# LNA_DIV.net
KiCad netlist of a schematic drawn in Altium Designer
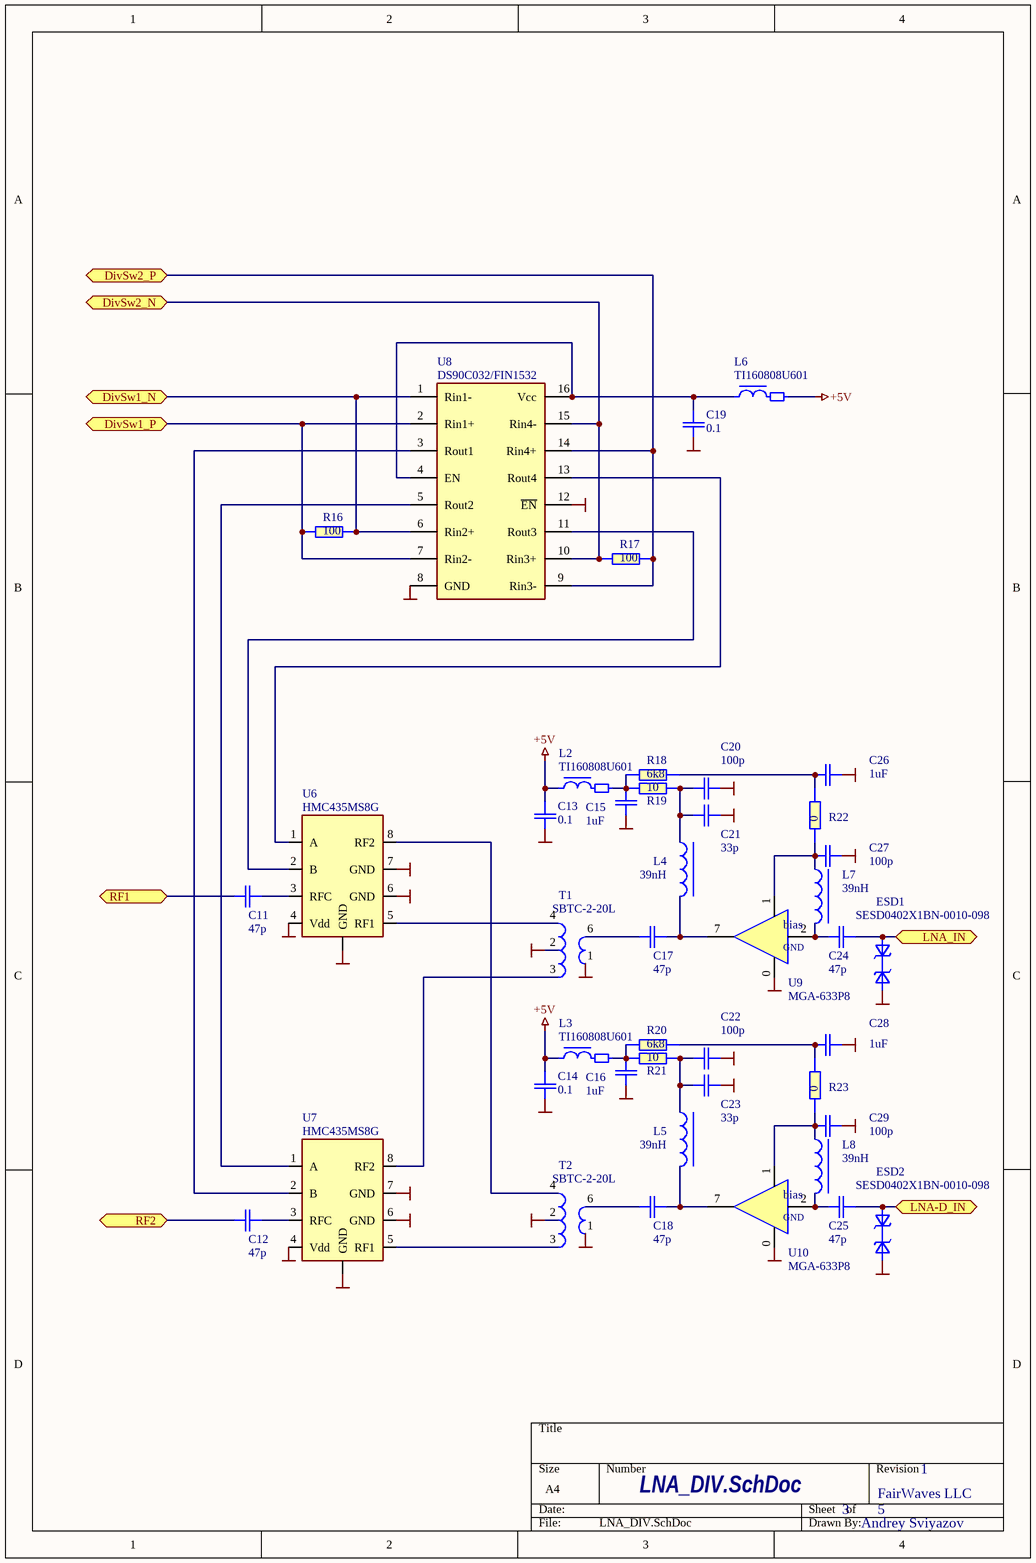
[diagram p0: LNA_DIV.SchDoc]

(export (version "E")
  (design (tool "Eeschema 10.0.6"))
  (components
    (comp (ref "C11")
      (value "47p")
      (footprint "C0603-PHILLIPS")
      (description "Capacitor")
      (fields (field (name "MANUFACTURER") "MURATA") (field (name "TOLERANCE") "20%"))
      (libsource (lib "altium-import") (part "root_1_C0603_"))
    )
    (comp (ref "C12")
      (value "47p")
      (footprint "C0603-PHILLIPS")
      (description "Capacitor")
      (fields (field (name "MANUFACTURER") "MURATA") (field (name "TOLERANCE") "20%"))
      (libsource (lib "altium-import") (part "root_1_C0603_"))
    )
    (comp (ref "C13")
      (value "0.1")
      (footprint "C0603-Phillips")
      (description "Capacitor")
      (fields (field (name "MANUFACTURER") "MURATA") (field (name "TOLERANCE") "20%"))
      (libsource (lib "Capacitors") (part "C0603"))
    )
    (comp (ref "C14")
      (value "0.1")
      (footprint "C0603-Phillips")
      (description "Capacitor")
      (fields (field (name "MANUFACTURER") "MURATA") (field (name "TOLERANCE") "20%"))
      (libsource (lib "Capacitors") (part "C0603"))
    )
    (comp (ref "C15")
      (value "1uF")
      (footprint "C0603-Phillips")
      (description "Capacitor")
      (fields (field (name "MANUFACTURER") "MURATA") (field (name "TOLERANCE") "20%"))
      (libsource (lib "Capacitors") (part "C0603"))
    )
    (comp (ref "C16")
      (value "1uF")
      (footprint "C0603-Phillips")
      (description "Capacitor")
      (fields (field (name "MANUFACTURER") "MURATA") (field (name "TOLERANCE") "20%"))
      (libsource (lib "Capacitors") (part "C0603"))
    )
    (comp (ref "C17")
      (value "47p")
      (footprint "C0603-PHILLIPS")
      (description "Capacitor")
      (fields (field (name "MANUFACTURER") "MURATA") (field (name "TOLERANCE") "20%"))
      (libsource (lib "altium-import") (part "root_1_C0603_"))
    )
    (comp (ref "C18")
      (value "47p")
      (footprint "C0603-PHILLIPS")
      (description "Capacitor")
      (fields (field (name "MANUFACTURER") "MURATA") (field (name "TOLERANCE") "20%"))
      (libsource (lib "altium-import") (part "root_1_C0603_"))
    )
    (comp (ref "C19")
      (value "0.1")
      (footprint "C0603-Phillips")
      (description "Capacitor")
      (fields (field (name "MANUFACTURER") "MURATA") (field (name "TOLERANCE") "20%"))
      (libsource (lib "Capacitors") (part "C0603"))
    )
    (comp (ref "C20")
      (value "100p")
      (footprint "C0603-PHILLIPS")
      (description "Capacitor")
      (fields (field (name "MANUFACTURER") "MURATA") (field (name "TOLERANCE") "20%"))
      (libsource (lib "altium-import") (part "root_1_C0603_"))
    )
    (comp (ref "C21")
      (value "33p")
      (footprint "C0603-PHILLIPS")
      (description "Capacitor")
      (fields (field (name "MANUFACTURER") "MURATA") (field (name "TOLERANCE") "20%"))
      (libsource (lib "altium-import") (part "root_1_C0603_"))
    )
    (comp (ref "C22")
      (value "100p")
      (footprint "C0603-PHILLIPS")
      (description "Capacitor")
      (fields (field (name "MANUFACTURER") "MURATA") (field (name "TOLERANCE") "20%"))
      (libsource (lib "altium-import") (part "root_1_C0603_"))
    )
    (comp (ref "C23")
      (value "33p")
      (footprint "C0603-PHILLIPS")
      (description "Capacitor")
      (fields (field (name "MANUFACTURER") "MURATA") (field (name "TOLERANCE") "20%"))
      (libsource (lib "altium-import") (part "root_1_C0603_"))
    )
    (comp (ref "C24")
      (value "47p")
      (footprint "C0603-PHILLIPS")
      (description "Capacitor")
      (fields (field (name "MANUFACTURER") "MURATA") (field (name "TOLERANCE") "20%"))
      (libsource (lib "altium-import") (part "root_1_C0603_"))
    )
    (comp (ref "C25")
      (value "47p")
      (footprint "C0603-PHILLIPS")
      (description "Capacitor")
      (fields (field (name "MANUFACTURER") "MURATA") (field (name "TOLERANCE") "20%"))
      (libsource (lib "altium-import") (part "root_1_C0603_"))
    )
    (comp (ref "C26")
      (value "1uF")
      (footprint "C0603-Phillips")
      (description "Capacitor")
      (fields (field (name "MANUFACTURER") "MURATA") (field (name "TOLERANCE") "20%"))
      (libsource (lib "Capacitors") (part "C0603"))
    )
    (comp (ref "C27")
      (value "100p")
      (footprint "C0603-PHILLIPS")
      (description "Capacitor")
      (fields (field (name "MANUFACTURER") "MURATA") (field (name "TOLERANCE") "20%"))
      (libsource (lib "altium-import") (part "root_1_C0603_"))
    )
    (comp (ref "C28")
      (value "1uF")
      (footprint "C0603-Phillips")
      (description "Capacitor")
      (fields (field (name "MANUFACTURER") "MURATA") (field (name "TOLERANCE") "20%"))
      (libsource (lib "Capacitors") (part "C0603"))
    )
    (comp (ref "C29")
      (value "100p")
      (footprint "C0603-PHILLIPS")
      (description "Capacitor")
      (fields (field (name "MANUFACTURER") "MURATA") (field (name "TOLERANCE") "20%"))
      (libsource (lib "altium-import") (part "root_1_C0603_"))
    )
    (comp (ref "ESD1")
      (value "SESD0402X1BN-0010-098")
      (footprint "R0402-Phillips")
      (description "ESD diod bi-directional")
      (fields (field (name "MANUFACTURER") "Tyco Electronics Corp"))
      (libsource (lib "*") (part "SESD0402X"))
    )
    (comp (ref "ESD2")
      (value "SESD0402X1BN-0010-098")
      (footprint "R0402-Phillips")
      (description "ESD diod bi-directional")
      (fields (field (name "MANUFACTURER") "Tyco Electronics Corp"))
      (libsource (lib "*") (part "SESD0402X"))
    )
    (comp (ref "L2")
      (value "TI160808U601")
      (footprint "Andy:Ti160808-Phillips")
      (description "Choke")
      (fields (field (name "MANUFACTURER") "MURATA"))
      (libsource (lib "altium-import") (part "root_0_TI160808_"))
    )
    (comp (ref "L3")
      (value "TI160808U601")
      (footprint "Andy:Ti160808-Phillips")
      (description "Choke")
      (fields (field (name "MANUFACTURER") "MURATA"))
      (libsource (lib "altium-import") (part "root_0_TI160808_"))
    )
    (comp (ref "L4")
      (value "39nH")
      (footprint "Andy:TF160808-Phillips")
      (description "Coil")
      (fields (field (name "MANUFACTURER") "SMD"))
      (libsource (lib "altium-import") (part "root_3_TF160808_"))
    )
    (comp (ref "L5")
      (value "39nH")
      (footprint "Andy:TF160808-Phillips")
      (description "Coil")
      (fields (field (name "MANUFACTURER") "SMD"))
      (libsource (lib "altium-import") (part "root_3_TF160808_"))
    )
    (comp (ref "L6")
      (value "TI160808U601")
      (footprint "Andy:Ti160808-Phillips")
      (description "Choke")
      (fields (field (name "MANUFACTURER") "MURATA"))
      (libsource (lib "altium-import") (part "root_0_TI160808_"))
    )
    (comp (ref "L7")
      (value "39nH")
      (footprint "Andy:TF160808-Phillips")
      (description "Coil")
      (fields (field (name "MANUFACTURER") "SMD"))
      (libsource (lib "altium-import") (part "root_3_TF160808_"))
    )
    (comp (ref "L8")
      (value "39nH")
      (footprint "Andy:TF160808-Phillips")
      (description "Coil")
      (fields (field (name "MANUFACTURER") "SMD"))
      (libsource (lib "altium-import") (part "root_3_TF160808_"))
    )
    (comp (ref "R16")
      (value "100")
      (footprint "R0603-PHILLIPS")
      (description "Resistor")
      (fields (field (name "MANUFACTURER") "YAGEO") (field (name "TOLERANCE") "5%"))
      (libsource (lib "altium-import") (part "root_1_R0603_"))
    )
    (comp (ref "R17")
      (value "100")
      (footprint "R0603-PHILLIPS")
      (description "Resistor")
      (fields (field (name "MANUFACTURER") "YAGEO") (field (name "TOLERANCE") "5%"))
      (libsource (lib "altium-import") (part "root_1_R0603_"))
    )
    (comp (ref "R18")
      (value "6k8")
      (footprint "R0603-PHILLIPS")
      (description "Resistor")
      (fields (field (name "MANUFACTURER") "YAGEO") (field (name "TOLERANCE") "5%"))
      (libsource (lib "altium-import") (part "root_1_R0603_"))
    )
    (comp (ref "R19")
      (value "10")
      (footprint "R0603-PHILLIPS")
      (description "Resistor")
      (fields (field (name "MANUFACTURER") "YAGEO") (field (name "TOLERANCE") "5%"))
      (libsource (lib "altium-import") (part "root_1_R0603_"))
    )
    (comp (ref "R20")
      (value "6k8")
      (footprint "R0603-PHILLIPS")
      (description "Resistor")
      (fields (field (name "MANUFACTURER") "YAGEO") (field (name "TOLERANCE") "5%"))
      (libsource (lib "altium-import") (part "root_1_R0603_"))
    )
    (comp (ref "R21")
      (value "10")
      (footprint "R0603-PHILLIPS")
      (description "Resistor")
      (fields (field (name "MANUFACTURER") "YAGEO") (field (name "TOLERANCE") "5%"))
      (libsource (lib "altium-import") (part "root_1_R0603_"))
    )
    (comp (ref "R22")
      (value "0")
      (footprint "R0603-PHILLIPS")
      (description "Resistor")
      (fields (field (name "MANUFACTURER") "YAGEO") (field (name "TOLERANCE") "5%"))
      (libsource (lib "altium-import") (part "root_2_R0603_"))
    )
    (comp (ref "R23")
      (value "0")
      (footprint "R0603-PHILLIPS")
      (description "Resistor")
      (fields (field (name "MANUFACTURER") "YAGEO") (field (name "TOLERANCE") "5%"))
      (libsource (lib "altium-import") (part "root_2_R0603_"))
    )
    (comp (ref "T1")
      (value "SBTC-2-20L")
      (footprint "AT1030")
      (description "Transformer")
      (fields (field (name "MANUFACTURER") "Mini-Cirquits"))
      (libsource (lib "altium-import") (part "root_0_mirrored_SBTC-2-10L_"))
    )
    (comp (ref "T2")
      (value "SBTC-2-20L")
      (footprint "AT1030")
      (description "Transformer")
      (fields (field (name "MANUFACTURER") "Mini-Cirquits"))
      (libsource (lib "altium-import") (part "root_0_mirrored_SBTC-2-10L_"))
    )
    (comp (ref "U6")
      (value "HMC435MS8G")
      (footprint "MS8G")
      (description "IC")
      (fields (field (name "MANUFACTURER") "Hittite"))
      (libsource (lib "altium-import") (part "root_0_HMC435MS8G_"))
    )
    (comp (ref "U7")
      (value "HMC435MS8G")
      (footprint "MS8G")
      (description "IC")
      (fields (field (name "MANUFACTURER") "Hittite"))
      (libsource (lib "altium-import") (part "root_0_HMC435MS8G_"))
    )
    (comp (ref "U8")
      (value "DS90C032/FIN1532")
      (footprint "SOIC16")
      (description "IC")
      (fields (field (name "MANUFACTURER") "National/Fairchild"))
      (libsource (lib "Andy") (part "DS90C032"))
    )
    (comp (ref "U9")
      (value "MGA-633P8")
      (footprint "SLP2x2")
      (description "IC")
      (fields (field (name "MANUFACTURER") "Avago"))
      (libsource (lib "altium-import") (part "root_0_mirrored_MGA-633P8_"))
    )
    (comp (ref "U10")
      (value "MGA-633P8")
      (footprint "SLP2x2")
      (description "IC")
      (fields (field (name "MANUFACTURER") "Avago"))
      (libsource (lib "altium-import") (part "root_0_mirrored_MGA-633P8_"))
    )
  )
  (nets
    (net (code "1") (name "+5V") (class "Default")
      (node (ref "C13") (pin "2") (pinfunction "2_2") (pintype "passive"))
      (node (ref "C14") (pin "2") (pinfunction "2_2") (pintype "passive"))
      (node (ref "L2") (pin "1") (pinfunction "1_1") (pintype "passive"))
      (node (ref "L3") (pin "1") (pinfunction "1_1") (pintype "passive"))
      (node (ref "L6") (pin "2") (pinfunction "2_2") (pintype "passive"))
    )
    (net (code "2") (name "/DivSw1_N") (class "Default")
      (node (ref "R16") (pin "2") (pinfunction "2_2") (pintype "passive"))
      (node (ref "U8") (pin "1") (pinfunction "Rin1-_1") (pintype "passive"))
      (node (ref "U8") (pin "6") (pinfunction "Rin2+_6") (pintype "power_in"))
    )
    (net (code "3") (name "/DivSw1_P") (class "Default")
      (node (ref "R16") (pin "1") (pinfunction "1_1") (pintype "passive"))
      (node (ref "U8") (pin "2") (pinfunction "Rin1+_2") (pintype "passive"))
      (node (ref "U8") (pin "7") (pinfunction "Rin2-_7") (pintype "passive"))
    )
    (net (code "4") (name "/DivSw2_N") (class "Default")
      (node (ref "R17") (pin "1") (pinfunction "1_1") (pintype "passive"))
      (node (ref "U8") (pin "10") (pinfunction "Rin3+_10") (pintype "passive"))
      (node (ref "U8") (pin "15") (pinfunction "Rin4-_15") (pintype "passive"))
    )
    (net (code "5") (name "/DivSw2_P") (class "Default")
      (node (ref "R17") (pin "2") (pinfunction "2_2") (pintype "passive"))
      (node (ref "U8") (pin "14") (pinfunction "Rin4+_14") (pintype "power_in"))
      (node (ref "U8") (pin "9") (pinfunction "Rin3-_9") (pintype "passive"))
    )
    (net (code "6") (name "/LNA-D_IN") (class "Default")
      (node (ref "C25") (pin "2") (pinfunction "2_2") (pintype "passive"))
      (node (ref "ESD2") (pin "2") (pinfunction "A2_2") (pintype "passive"))
    )
    (net (code "7") (name "/LNA_IN") (class "Default")
      (node (ref "C24") (pin "2") (pinfunction "2_2") (pintype "passive"))
      (node (ref "ESD1") (pin "2") (pinfunction "A2_2") (pintype "passive"))
    )
    (net (code "8") (name "/RF1") (class "Default")
      (node (ref "C11") (pin "1") (pinfunction "1_1") (pintype "passive"))
    )
    (net (code "9") (name "/RF2") (class "Default")
      (node (ref "C12") (pin "1") (pinfunction "1_1") (pintype "passive"))
    )
    (net (code "10") (name "GND") (class "Default")
      (node (ref "C13") (pin "1") (pinfunction "1_1") (pintype "passive"))
      (node (ref "C14") (pin "1") (pinfunction "1_1") (pintype "passive"))
      (node (ref "C15") (pin "1") (pinfunction "1_1") (pintype "passive"))
      (node (ref "C16") (pin "1") (pinfunction "1_1") (pintype "passive"))
      (node (ref "C19") (pin "1") (pinfunction "1_1") (pintype "passive"))
      (node (ref "C20") (pin "2") (pinfunction "2_2") (pintype "passive"))
      (node (ref "C21") (pin "2") (pinfunction "2_2") (pintype "passive"))
      (node (ref "C22") (pin "2") (pinfunction "2_2") (pintype "passive"))
      (node (ref "C23") (pin "2") (pinfunction "2_2") (pintype "passive"))
      (node (ref "C26") (pin "2") (pinfunction "2_2") (pintype "passive"))
      (node (ref "C27") (pin "2") (pinfunction "2_2") (pintype "passive"))
      (node (ref "C28") (pin "2") (pinfunction "2_2") (pintype "passive"))
      (node (ref "C29") (pin "2") (pinfunction "2_2") (pintype "passive"))
      (node (ref "ESD1") (pin "1") (pinfunction "A1_1") (pintype "passive"))
      (node (ref "ESD2") (pin "1") (pinfunction "A1_1") (pintype "passive"))
      (node (ref "T1") (pin "1") (pinfunction "1_1") (pintype "passive"))
      (node (ref "T1") (pin "2") (pinfunction "2_2") (pintype "passive"))
      (node (ref "T2") (pin "1") (pinfunction "1_1") (pintype "passive"))
      (node (ref "T2") (pin "2") (pinfunction "2_2") (pintype "passive"))
      (node (ref "U10") (pin "0") (pinfunction "GND_0") (pintype "power_in"))
      (node (ref "U6") (pin "0") (pinfunction "GND_0") (pintype "power_in"))
      (node (ref "U6") (pin "4") (pinfunction "Vdd_4") (pintype "power_in"))
      (node (ref "U6") (pin "6") (pinfunction "GND_6") (pintype "power_in"))
      (node (ref "U6") (pin "7") (pinfunction "GND_7") (pintype "power_in"))
      (node (ref "U7") (pin "0") (pinfunction "GND_0") (pintype "power_in"))
      (node (ref "U7") (pin "4") (pinfunction "Vdd_4") (pintype "power_in"))
      (node (ref "U7") (pin "6") (pinfunction "GND_6") (pintype "power_in"))
      (node (ref "U7") (pin "7") (pinfunction "GND_7") (pintype "power_in"))
      (node (ref "U8") (pin "12") (pinfunction "~{EN}_12") (pintype "passive"))
      (node (ref "U8") (pin "8") (pinfunction "GND_8") (pintype "passive"))
      (node (ref "U9") (pin "0") (pinfunction "GND_0") (pintype "power_in"))
    )
    (net (code "11") (name "Net-(C15-Pad2)") (class "Default")
      (node (ref "C15") (pin "2") (pinfunction "2_2") (pintype "passive"))
      (node (ref "L2") (pin "2") (pinfunction "2_2") (pintype "passive"))
      (node (ref "R18") (pin "1") (pinfunction "1_1") (pintype "passive"))
      (node (ref "R19") (pin "1") (pinfunction "1_1") (pintype "passive"))
    )
    (net (code "12") (name "Net-(C16-Pad2)") (class "Default")
      (node (ref "C16") (pin "2") (pinfunction "2_2") (pintype "passive"))
      (node (ref "L3") (pin "2") (pinfunction "2_2") (pintype "passive"))
      (node (ref "R20") (pin "1") (pinfunction "1_1") (pintype "passive"))
      (node (ref "R21") (pin "1") (pinfunction "1_1") (pintype "passive"))
    )
    (net (code "13") (name "Net-(C17-Pad1)") (class "Default")
      (node (ref "C17") (pin "1") (pinfunction "1_1") (pintype "passive"))
      (node (ref "T1") (pin "6") (pinfunction "6_6") (pintype "passive"))
    )
    (net (code "14") (name "Net-(C18-Pad1)") (class "Default")
      (node (ref "C18") (pin "1") (pinfunction "1_1") (pintype "passive"))
      (node (ref "T2") (pin "6") (pinfunction "6_6") (pintype "passive"))
    )
    (net (code "15") (name "Net-(C20-Pad1)") (class "Default")
      (node (ref "C20") (pin "1") (pinfunction "1_1") (pintype "passive"))
      (node (ref "C21") (pin "1") (pinfunction "1_1") (pintype "passive"))
      (node (ref "L4") (pin "1") (pinfunction "1_1") (pintype "passive"))
      (node (ref "R19") (pin "2") (pinfunction "2_2") (pintype "passive"))
    )
    (net (code "16") (name "Net-(C22-Pad1)") (class "Default")
      (node (ref "C22") (pin "1") (pinfunction "1_1") (pintype "passive"))
      (node (ref "C23") (pin "1") (pinfunction "1_1") (pintype "passive"))
      (node (ref "L5") (pin "1") (pinfunction "1_1") (pintype "passive"))
      (node (ref "R21") (pin "2") (pinfunction "2_2") (pintype "passive"))
    )
    (net (code "17") (name "Net-(C26-Pad1)") (class "Default")
      (node (ref "C26") (pin "1") (pinfunction "1_1") (pintype "passive"))
      (node (ref "R18") (pin "2") (pinfunction "2_2") (pintype "passive"))
      (node (ref "R22") (pin "2") (pinfunction "2_2") (pintype "passive"))
    )
    (net (code "18") (name "Net-(C28-Pad1)") (class "Default")
      (node (ref "C28") (pin "1") (pinfunction "1_1") (pintype "passive"))
      (node (ref "R20") (pin "2") (pinfunction "2_2") (pintype "passive"))
      (node (ref "R23") (pin "2") (pinfunction "2_2") (pintype "passive"))
    )
    (net (code "19") (name "Net-(U6-A)") (class "Default")
      (node (ref "U6") (pin "1") (pinfunction "A_1") (pintype "passive"))
      (node (ref "U8") (pin "13") (pinfunction "Rout4_13") (pintype "passive"))
    )
    (net (code "20") (name "Net-(U6-B)") (class "Default")
      (node (ref "U6") (pin "2") (pinfunction "B_2") (pintype "passive"))
      (node (ref "U8") (pin "11") (pinfunction "Rout3_11") (pintype "passive"))
    )
    (net (code "21") (name "Net-(U6-RF1)") (class "Default")
      (node (ref "T1") (pin "4") (pinfunction "4_4") (pintype "passive"))
      (node (ref "U6") (pin "5") (pinfunction "RF1_5") (pintype "passive"))
    )
    (net (code "22") (name "Net-(U6-RF2)") (class "Default")
      (node (ref "T2") (pin "4") (pinfunction "4_4") (pintype "passive"))
      (node (ref "U6") (pin "8") (pinfunction "RF2_8") (pintype "passive"))
    )
    (net (code "23") (name "Net-(U6-RFC)") (class "Default")
      (node (ref "C11") (pin "2") (pinfunction "2_2") (pintype "passive"))
      (node (ref "U6") (pin "3") (pinfunction "RFC_3") (pintype "power_in"))
    )
    (net (code "24") (name "Net-(U7-A)") (class "Default")
      (node (ref "U7") (pin "1") (pinfunction "A_1") (pintype "passive"))
      (node (ref "U8") (pin "5") (pinfunction "Rout2_5") (pintype "passive"))
    )
    (net (code "25") (name "Net-(U7-B)") (class "Default")
      (node (ref "U7") (pin "2") (pinfunction "B_2") (pintype "passive"))
      (node (ref "U8") (pin "3") (pinfunction "Rout1_3") (pintype "passive"))
    )
    (net (code "26") (name "Net-(U7-RF1)") (class "Default")
      (node (ref "T2") (pin "3") (pinfunction "3_3") (pintype "passive"))
      (node (ref "U7") (pin "5") (pinfunction "RF1_5") (pintype "passive"))
    )
    (net (code "27") (name "Net-(U7-RF2)") (class "Default")
      (node (ref "T1") (pin "3") (pinfunction "3_3") (pintype "passive"))
      (node (ref "U7") (pin "8") (pinfunction "RF2_8") (pintype "passive"))
    )
    (net (code "28") (name "Net-(U7-RFC)") (class "Default")
      (node (ref "C12") (pin "2") (pinfunction "2_2") (pintype "passive"))
      (node (ref "U7") (pin "3") (pinfunction "RFC_3") (pintype "power_in"))
    )
    (net (code "29") (name "Net-(U8-EN)") (class "Default")
      (node (ref "C19") (pin "2") (pinfunction "2_2") (pintype "passive"))
      (node (ref "L6") (pin "1") (pinfunction "1_1") (pintype "passive"))
      (node (ref "U8") (pin "16") (pinfunction "Vcc_16") (pintype "passive"))
      (node (ref "U8") (pin "4") (pinfunction "EN_4") (pintype "passive"))
    )
    (net (code "30") (name "Net-(U9-A)") (class "Default")
      (node (ref "C24") (pin "1") (pinfunction "1_1") (pintype "passive"))
      (node (ref "L7") (pin "2") (pinfunction "2_2") (pintype "passive"))
      (node (ref "U9") (pin "2") (pinfunction "A_2") (pintype "passive"))
    )
    (net (code "31") (name "Net-(U9-BIAS)") (class "Default")
      (node (ref "C27") (pin "1") (pinfunction "1_1") (pintype "passive"))
      (node (ref "L7") (pin "1") (pinfunction "1_1") (pintype "passive"))
      (node (ref "R22") (pin "1") (pinfunction "1_1") (pintype "passive"))
      (node (ref "U9") (pin "1") (pinfunction "BIAS_1") (pintype "passive"))
    )
    (net (code "32") (name "Net-(U9-RFout{slash}VDD)") (class "Default")
      (node (ref "C17") (pin "2") (pinfunction "2_2") (pintype "passive"))
      (node (ref "L4") (pin "2") (pinfunction "2_2") (pintype "passive"))
      (node (ref "U9") (pin "7") (pinfunction "RFout/VDD_7") (pintype "passive"))
    )
    (net (code "33") (name "Net-(U10-A)") (class "Default")
      (node (ref "C25") (pin "1") (pinfunction "1_1") (pintype "passive"))
      (node (ref "L8") (pin "2") (pinfunction "2_2") (pintype "passive"))
      (node (ref "U10") (pin "2") (pinfunction "A_2") (pintype "passive"))
    )
    (net (code "34") (name "Net-(U10-BIAS)") (class "Default")
      (node (ref "C29") (pin "1") (pinfunction "1_1") (pintype "passive"))
      (node (ref "L8") (pin "1") (pinfunction "1_1") (pintype "passive"))
      (node (ref "R23") (pin "1") (pinfunction "1_1") (pintype "passive"))
      (node (ref "U10") (pin "1") (pinfunction "BIAS_1") (pintype "passive"))
    )
    (net (code "35") (name "Net-(U10-RFout{slash}VDD)") (class "Default")
      (node (ref "C18") (pin "2") (pinfunction "2_2") (pintype "passive"))
      (node (ref "L5") (pin "2") (pinfunction "2_2") (pintype "passive"))
      (node (ref "U10") (pin "7") (pinfunction "RFout/VDD_7") (pintype "passive"))
    )
  )
)
